# Middle_Arduino.net
KiCad netlist of a schematic drawn in Altium Designer
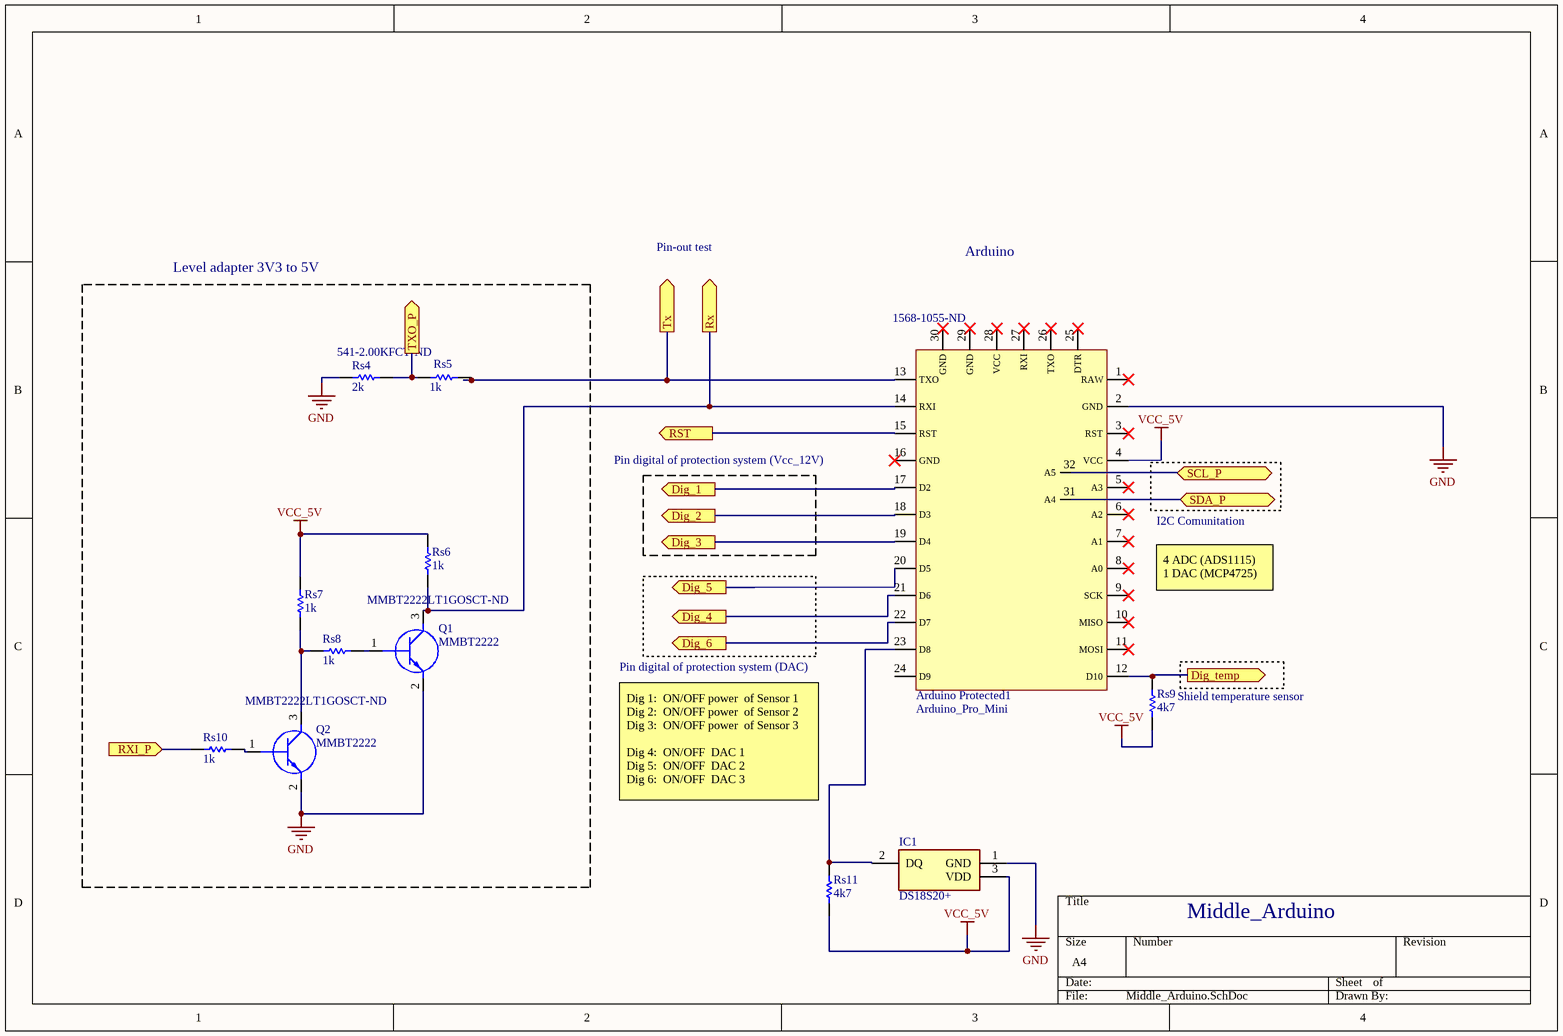
[diagram p0: Middle_Arduino.SchDoc]

(export (version "E")
  (design (tool "Eeschema 10.0.6"))
  (components
    (comp (ref "Arduino Protected1")
      (value "Arduino_Pro_Mini")
      (footprint "Arduino_Pro_Mini")
      (fields (field (name "SUPPLIER PART NUMBER 1") "1568-1055-ND"))
      (libsource (lib "Middle_Symbols") (part "Arduino_Pro_Mini"))
    )
    (comp (ref "IC1")
      (value "DS18S20+")
      (footprint "ONSC-TO-92-3-29-11_AM_BL")
      (description "Integrated Circuit")
      (fields (field (name "MOUSER PART NUMBER") "700-DS18S20"))
      (libsource (lib "Middle_Symbols") (part "DS18S20+"))
    )
    (comp (ref "Q1")
      (value "MMBT2222")
      (footprint "SamacSys:SOT95P240X114-3N")
      (description "Transistor BJT NPN")
      (fields
        (field (name "MOUSER PART NUMBER") "512-MMBT2222")
        (field (name "SUPPLIER PART NUMBER 1") "MMBT2222LT1GOSCT-ND")
      )
      (libsource (lib "*") (part "MMBT2222"))
    )
    (comp (ref "Q2")
      (value "MMBT2222")
      (footprint "SamacSys:SOT95P240X114-3N")
      (description "Transistor BJT NPN")
      (fields
        (field (name "MOUSER PART NUMBER") "512-MMBT2222")
        (field (name "SUPPLIER PART NUMBER 1") "MMBT2222LT1GOSCT-ND")
      )
      (libsource (lib "*") (part "MMBT2222"))
    )
    (comp (ref "Rs4")
      (value "2k")
      (footprint "R1206")
      (description "1206 Resistor  1% CMP2010A 1Watt 100ppm")
      (fields (field (name "SUPPLIER PART NUMBER 1") "541-2.00KFCT-ND"))
      (libsource (lib "Middle_Symbols") (part "R1206"))
    )
    (comp (ref "Rs5")
      (value "1k")
      (footprint "R1206")
      (description "1206 Resistor  1% CMP2010A 1Watt 100ppm")
      (libsource (lib "Middle_Symbols") (part "R1206"))
    )
    (comp (ref "Rs6")
      (value "1k")
      (footprint "R1206")
      (description "1206 Resistor  1% CMP2010A 1Watt 100ppm")
      (libsource (lib "Middle_Symbols") (part "R1206"))
    )
    (comp (ref "Rs7")
      (value "1k")
      (footprint "R1206")
      (description "1206 Resistor  1% CMP2010A 1Watt 100ppm")
      (libsource (lib "Middle_Symbols") (part "R1206"))
    )
    (comp (ref "Rs8")
      (value "1k")
      (footprint "R1206")
      (description "1206 Resistor  1% CMP2010A 1Watt 100ppm")
      (libsource (lib "Middle_Symbols") (part "R1206"))
    )
    (comp (ref "Rs9")
      (value "4k7")
      (footprint "R1206")
      (description "1206 Resistor  1% CMP2010A 1Watt 100ppm")
      (libsource (lib "Middle_Symbols") (part "R1206"))
    )
    (comp (ref "Rs10")
      (value "1k")
      (footprint "R1206")
      (description "1206 Resistor  1% CMP2010A 1Watt 100ppm")
      (libsource (lib "Middle_Symbols") (part "R1206"))
    )
    (comp (ref "Rs11")
      (value "4k7")
      (footprint "R1206")
      (description "1206 Resistor  1% CMP2010A 1Watt 100ppm")
      (libsource (lib "Middle_Symbols") (part "R1206"))
    )
  )
  (nets
    (net (code "1") (name "/Dig_1") (class "Default")
      (node (ref "Arduino Protected1") (pin "17") (pinfunction "D2_17") (pintype "passive"))
    )
    (net (code "2") (name "/Dig_2") (class "Default")
      (node (ref "Arduino Protected1") (pin "18") (pinfunction "D3_18") (pintype "passive"))
    )
    (net (code "3") (name "/Dig_3") (class "Default")
      (node (ref "Arduino Protected1") (pin "19") (pinfunction "D4_19") (pintype "passive"))
    )
    (net (code "4") (name "/Dig_4") (class "Default")
      (node (ref "Arduino Protected1") (pin "21") (pinfunction "D6_21") (pintype "passive"))
    )
    (net (code "5") (name "/Dig_5") (class "Default")
      (node (ref "Arduino Protected1") (pin "20") (pinfunction "D5_20") (pintype "passive"))
    )
    (net (code "6") (name "/Dig_6") (class "Default")
      (node (ref "Arduino Protected1") (pin "22") (pinfunction "D7_22") (pintype "passive"))
    )
    (net (code "7") (name "/Dig_temp") (class "Default")
      (node (ref "Arduino Protected1") (pin "12") (pinfunction "D10_12") (pintype "passive"))
      (node (ref "Rs9") (pin "2") (pinfunction "2_2") (pintype "passive"))
    )
    (net (code "8") (name "/RST") (class "Default")
      (node (ref "Arduino Protected1") (pin "15") (pinfunction "RST_15") (pintype "passive"))
    )
    (net (code "9") (name "/RXI_P") (class "Default")
      (node (ref "Rs10") (pin "1") (pinfunction "1_1") (pintype "passive"))
    )
    (net (code "10") (name "/Rx") (class "Default")
      (node (ref "Arduino Protected1") (pin "14") (pinfunction "RXI_14") (pintype "passive"))
      (node (ref "Q1") (pin "3") (pinfunction "C_3") (pintype "passive"))
      (node (ref "Rs6") (pin "1") (pinfunction "1_1") (pintype "passive"))
    )
    (net (code "11") (name "/SCL_P") (class "Default")
      (node (ref "Arduino Protected1") (pin "32") (pinfunction "A5_32") (pintype "passive"))
    )
    (net (code "12") (name "/SDA_P") (class "Default")
      (node (ref "Arduino Protected1") (pin "31") (pinfunction "A4_31") (pintype "passive"))
    )
    (net (code "13") (name "/TXO_P") (class "Default")
      (node (ref "Rs4") (pin "2") (pinfunction "2_2") (pintype "passive"))
      (node (ref "Rs5") (pin "1") (pinfunction "1_1") (pintype "passive"))
    )
    (net (code "14") (name "/Tx") (class "Default")
      (node (ref "Arduino Protected1") (pin "13") (pinfunction "TXO_13") (pintype "passive"))
      (node (ref "Rs5") (pin "2") (pinfunction "2_2") (pintype "passive"))
    )
    (net (code "15") (name "GND") (class "Default")
      (node (ref "Arduino Protected1") (pin "2") (pinfunction "GND_2") (pintype "power_in"))
      (node (ref "IC1") (pin "1") (pinfunction "GND_1") (pintype "passive"))
      (node (ref "Q1") (pin "2") (pinfunction "E_2") (pintype "passive"))
      (node (ref "Q2") (pin "2") (pinfunction "E_2") (pintype "passive"))
      (node (ref "Rs4") (pin "1") (pinfunction "1_1") (pintype "passive"))
    )
    (net (code "16") (name "Net-(Arduino Protected1-D8)") (class "Default")
      (node (ref "Arduino Protected1") (pin "23") (pinfunction "D8_23") (pintype "passive"))
      (node (ref "IC1") (pin "2") (pinfunction "DQ_2") (pintype "passive"))
      (node (ref "Rs11") (pin "2") (pinfunction "2_2") (pintype "passive"))
    )
    (net (code "17") (name "Net-(Q1-B)") (class "Default")
      (node (ref "Q1") (pin "1") (pinfunction "B_1") (pintype "passive"))
      (node (ref "Rs8") (pin "1") (pinfunction "1_1") (pintype "passive"))
    )
    (net (code "18") (name "Net-(Q2-B)") (class "Default")
      (node (ref "Q2") (pin "1") (pinfunction "B_1") (pintype "passive"))
      (node (ref "Rs10") (pin "2") (pinfunction "2_2") (pintype "passive"))
    )
    (net (code "19") (name "Net-(Q2-C)") (class "Default")
      (node (ref "Q2") (pin "3") (pinfunction "C_3") (pintype "passive"))
      (node (ref "Rs7") (pin "1") (pinfunction "1_1") (pintype "passive"))
      (node (ref "Rs8") (pin "2") (pinfunction "2_2") (pintype "passive"))
    )
    (net (code "20") (name "VCC_5V") (class "Default")
      (node (ref "Arduino Protected1") (pin "4") (pinfunction "VCC_4") (pintype "power_in"))
      (node (ref "IC1") (pin "3") (pinfunction "VDD_3") (pintype "passive"))
      (node (ref "Rs11") (pin "1") (pinfunction "1_1") (pintype "passive"))
      (node (ref "Rs6") (pin "2") (pinfunction "2_2") (pintype "passive"))
      (node (ref "Rs7") (pin "2") (pinfunction "2_2") (pintype "passive"))
      (node (ref "Rs9") (pin "1") (pinfunction "1_1") (pintype "passive"))
    )
    (net (code "21") (name "unconnected-(Arduino Protected1-A0-Pad8)") (class "Default")
      (node (ref "Arduino Protected1") (pin "8") (pinfunction "A0_8") (pintype "passive+no_connect"))
    )
    (net (code "22") (name "unconnected-(Arduino Protected1-A1-Pad7)") (class "Default")
      (node (ref "Arduino Protected1") (pin "7") (pinfunction "A1_7") (pintype "passive+no_connect"))
    )
    (net (code "23") (name "unconnected-(Arduino Protected1-A2-Pad6)") (class "Default")
      (node (ref "Arduino Protected1") (pin "6") (pinfunction "A2_6") (pintype "passive+no_connect"))
    )
    (net (code "24") (name "unconnected-(Arduino Protected1-A3-Pad5)") (class "Default")
      (node (ref "Arduino Protected1") (pin "5") (pinfunction "A3_5") (pintype "passive+no_connect"))
    )
    (net (code "25") (name "unconnected-(Arduino Protected1-D9-Pad24)") (class "Default")
      (node (ref "Arduino Protected1") (pin "24") (pinfunction "D9_24") (pintype "passive"))
    )
    (net (code "26") (name "unconnected-(Arduino Protected1-DTR-Pad25)") (class "Default")
      (node (ref "Arduino Protected1") (pin "25") (pinfunction "DTR_25") (pintype "passive+no_connect"))
    )
    (net (code "27") (name "unconnected-(Arduino Protected1-GND-Pad16)") (class "Default")
      (node (ref "Arduino Protected1") (pin "16") (pinfunction "GND_16") (pintype "passive+no_connect"))
    )
    (net (code "28") (name "unconnected-(Arduino Protected1-GND-Pad29)") (class "Default")
      (node (ref "Arduino Protected1") (pin "29") (pinfunction "GND_29") (pintype "passive+no_connect"))
    )
    (net (code "29") (name "unconnected-(Arduino Protected1-GND-Pad30)") (class "Default")
      (node (ref "Arduino Protected1") (pin "30") (pinfunction "GND_30") (pintype "passive+no_connect"))
    )
    (net (code "30") (name "unconnected-(Arduino Protected1-MISO-Pad10)") (class "Default")
      (node (ref "Arduino Protected1") (pin "10") (pinfunction "MISO_10") (pintype "passive+no_connect"))
    )
    (net (code "31") (name "unconnected-(Arduino Protected1-MOSI-Pad11)") (class "Default")
      (node (ref "Arduino Protected1") (pin "11") (pinfunction "MOSI_11") (pintype "passive+no_connect"))
    )
    (net (code "32") (name "unconnected-(Arduino Protected1-RAW-Pad1)") (class "Default")
      (node (ref "Arduino Protected1") (pin "1") (pinfunction "RAW_1") (pintype "power_in+no_connect"))
    )
    (net (code "33") (name "unconnected-(Arduino Protected1-RST-Pad3)") (class "Default")
      (node (ref "Arduino Protected1") (pin "3") (pinfunction "RST_3") (pintype "passive+no_connect"))
    )
    (net (code "34") (name "unconnected-(Arduino Protected1-RXI-Pad27)") (class "Default")
      (node (ref "Arduino Protected1") (pin "27") (pinfunction "RXI_27") (pintype "passive+no_connect"))
    )
    (net (code "35") (name "unconnected-(Arduino Protected1-SCK-Pad9)") (class "Default")
      (node (ref "Arduino Protected1") (pin "9") (pinfunction "SCK_9") (pintype "passive+no_connect"))
    )
    (net (code "36") (name "unconnected-(Arduino Protected1-TXO-Pad26)") (class "Default")
      (node (ref "Arduino Protected1") (pin "26") (pinfunction "TXO_26") (pintype "passive+no_connect"))
    )
    (net (code "37") (name "unconnected-(Arduino Protected1-VCC-Pad28)") (class "Default")
      (node (ref "Arduino Protected1") (pin "28") (pinfunction "VCC_28") (pintype "passive+no_connect"))
    )
  )
)
